# ModuleGliderScore.net
KiCad netlist of a schematic drawn in EAGLE
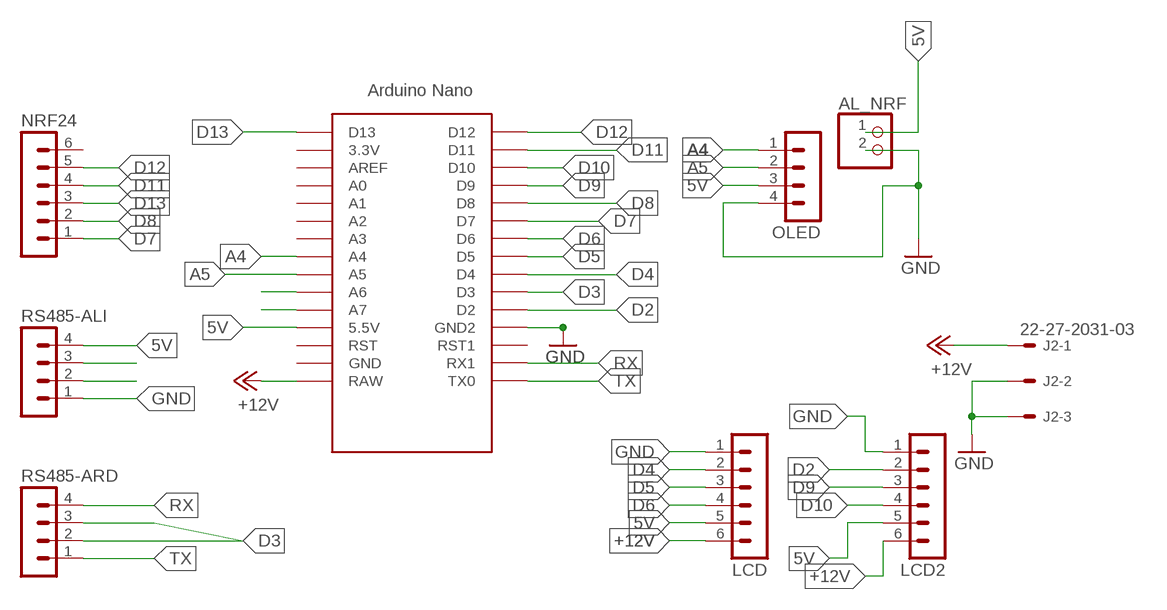
[diagram p0: schematic, sheet 1]

(export (version "E")
  (design (tool "Eeschema 10.0.6"))
  (components
    (comp (ref "AL_NRF")
      (value "PINHD-1X2")
      (footprint "eagle-import:1X02")
      (libsource (lib "eagle-import") (part "PINHD-1X2"))
    )
    (comp (ref "J2")
      (value "22-27-2031-03")
      (footprint "eagle-import:6410-03")
      (libsource (lib "eagle-import") (part "22-?-0327-2031"))
    )
    (comp (ref "LCD")
      (value "MA06-1")
      (footprint "eagle-import:MA06-1")
      (libsource (lib "eagle-import") (part "MA06-1"))
    )
    (comp (ref "LCD2")
      (value "MA06-1")
      (footprint "eagle-import:MA06-1")
      (libsource (lib "eagle-import") (part "MA06-1"))
    )
    (comp (ref "NRF24")
      (value "MA06-1")
      (footprint "eagle-import:MA06-1")
      (libsource (lib "eagle-import") (part "MA06-1"))
    )
    (comp (ref "OLED")
      (value "MA04-1")
      (footprint "eagle-import:MA04-1")
      (libsource (lib "eagle-import") (part "MA04-1"))
    )
    (comp (ref "RS485-ALI")
      (value "MA04-1")
      (footprint "eagle-import:MA04-1")
      (libsource (lib "eagle-import") (part "MA04-1"))
    )
    (comp (ref "RS485-ARD")
      (value "MA04-1")
      (footprint "eagle-import:MA04-1")
      (libsource (lib "eagle-import") (part "MA04-1"))
    )
    (comp (ref "U$1")
      (value "NANO")
      (footprint "eagle-import:NANO")
      (libsource (lib "eagle-import") (part "NANO"))
    )
  )
  (nets
    (net (code "1") (name "+12V") (class "Default")
      (node (ref "J2") (pin "1") (pinfunction "S_1") (pintype "passive"))
      (node (ref "LCD") (pin "6") (pinfunction "6_6") (pintype "passive"))
      (node (ref "LCD2") (pin "6") (pinfunction "6_6") (pintype "passive"))
      (node (ref "U$1") (pin "RAW") (pinfunction "RAW_RAW") (pintype "bidirectional"))
    )
    (net (code "2") (name "5V") (class "Default")
      (node (ref "AL_NRF") (pin "1") (pinfunction "1_1") (pintype "passive"))
      (node (ref "LCD") (pin "5") (pinfunction "5_5") (pintype "passive"))
      (node (ref "LCD2") (pin "5") (pinfunction "5_5") (pintype "passive"))
      (node (ref "OLED") (pin "3") (pinfunction "3_3") (pintype "passive"))
      (node (ref "RS485-ALI") (pin "4") (pinfunction "4_4") (pintype "passive"))
      (node (ref "U$1") (pin "5V") (pinfunction "5.5V_5V") (pintype "bidirectional"))
    )
    (net (code "3") (name "A4") (class "Default")
      (node (ref "OLED") (pin "1") (pinfunction "1_1") (pintype "passive"))
      (node (ref "U$1") (pin "A4") (pinfunction "A4_A4") (pintype "bidirectional"))
    )
    (net (code "4") (name "A5") (class "Default")
      (node (ref "OLED") (pin "2") (pinfunction "2_2") (pintype "passive"))
      (node (ref "U$1") (pin "A5") (pinfunction "A5_A5") (pintype "bidirectional"))
    )
    (net (code "5") (name "D2") (class "Default")
      (node (ref "LCD2") (pin "2") (pinfunction "2_2") (pintype "passive"))
      (node (ref "U$1") (pin "D2") (pinfunction "D2_D2") (pintype "bidirectional"))
    )
    (net (code "6") (name "D3") (class "Default")
      (node (ref "RS485-ARD") (pin "2") (pinfunction "2_2") (pintype "passive"))
      (node (ref "RS485-ARD") (pin "3") (pinfunction "3_3") (pintype "passive"))
      (node (ref "U$1") (pin "D3") (pinfunction "D3_D3") (pintype "bidirectional"))
    )
    (net (code "7") (name "D4") (class "Default")
      (node (ref "LCD") (pin "2") (pinfunction "2_2") (pintype "passive"))
      (node (ref "U$1") (pin "D4") (pinfunction "D4_D4") (pintype "bidirectional"))
    )
    (net (code "8") (name "D5") (class "Default")
      (node (ref "LCD") (pin "3") (pinfunction "3_3") (pintype "passive"))
      (node (ref "U$1") (pin "D5") (pinfunction "D5_D5") (pintype "bidirectional"))
    )
    (net (code "9") (name "D6") (class "Default")
      (node (ref "LCD") (pin "4") (pinfunction "4_4") (pintype "passive"))
      (node (ref "U$1") (pin "D6") (pinfunction "D6_D6") (pintype "bidirectional"))
    )
    (net (code "10") (name "D7") (class "Default")
      (node (ref "NRF24") (pin "1") (pinfunction "1_1") (pintype "passive"))
      (node (ref "U$1") (pin "D7") (pinfunction "D7_D7") (pintype "bidirectional"))
    )
    (net (code "11") (name "D8") (class "Default")
      (node (ref "NRF24") (pin "2") (pinfunction "2_2") (pintype "passive"))
      (node (ref "U$1") (pin "D8") (pinfunction "D8_D8") (pintype "bidirectional"))
    )
    (net (code "12") (name "D9") (class "Default")
      (node (ref "LCD2") (pin "3") (pinfunction "3_3") (pintype "passive"))
      (node (ref "U$1") (pin "D9") (pinfunction "D9_D9") (pintype "bidirectional"))
    )
    (net (code "13") (name "D10") (class "Default")
      (node (ref "LCD2") (pin "4") (pinfunction "4_4") (pintype "passive"))
      (node (ref "U$1") (pin "D10") (pinfunction "D10_D10") (pintype "bidirectional"))
    )
    (net (code "14") (name "D11") (class "Default")
      (node (ref "NRF24") (pin "4") (pinfunction "4_4") (pintype "passive"))
      (node (ref "U$1") (pin "D11") (pinfunction "D11_D11") (pintype "bidirectional"))
    )
    (net (code "15") (name "D12") (class "Default")
      (node (ref "NRF24") (pin "5") (pinfunction "5_5") (pintype "passive"))
      (node (ref "U$1") (pin "D12") (pinfunction "D12_D12") (pintype "bidirectional"))
    )
    (net (code "16") (name "D13") (class "Default")
      (node (ref "NRF24") (pin "3") (pinfunction "3_3") (pintype "passive"))
      (node (ref "U$1") (pin "D13") (pinfunction "D13_D13") (pintype "bidirectional"))
    )
    (net (code "17") (name "GND") (class "Default")
      (node (ref "AL_NRF") (pin "2") (pinfunction "2_2") (pintype "passive"))
      (node (ref "J2") (pin "2") (pinfunction "S_2") (pintype "passive"))
      (node (ref "J2") (pin "3") (pinfunction "S_3") (pintype "passive"))
      (node (ref "LCD") (pin "1") (pinfunction "1_1") (pintype "passive"))
      (node (ref "LCD2") (pin "1") (pinfunction "1_1") (pintype "passive"))
      (node (ref "OLED") (pin "4") (pinfunction "4_4") (pintype "passive"))
      (node (ref "RS485-ALI") (pin "1") (pinfunction "1_1") (pintype "passive"))
      (node (ref "U$1") (pin "GND1") (pinfunction "GND2_GND1") (pintype "bidirectional"))
    )
    (net (code "18") (name "RX") (class "Default")
      (node (ref "RS485-ARD") (pin "4") (pinfunction "4_4") (pintype "passive"))
      (node (ref "U$1") (pin "RX1") (pinfunction "RX1_RX1") (pintype "bidirectional"))
    )
    (net (code "19") (name "TX") (class "Default")
      (node (ref "RS485-ARD") (pin "1") (pinfunction "1_1") (pintype "passive"))
      (node (ref "U$1") (pin "TX0") (pinfunction "TX0_TX0") (pintype "bidirectional"))
    )
    (net (code "20") (name "unconnected-(NRF24-Pad6)") (class "Default")
      (node (ref "NRF24") (pin "6") (pinfunction "6_6") (pintype "passive"))
    )
    (net (code "21") (name "unconnected-(RS485-ALI-Pad2)") (class "Default")
      (node (ref "RS485-ALI") (pin "2") (pinfunction "2_2") (pintype "passive"))
    )
    (net (code "22") (name "unconnected-(RS485-ALI-Pad3)") (class "Default")
      (node (ref "RS485-ALI") (pin "3") (pinfunction "3_3") (pintype "passive"))
    )
    (net (code "23") (name "unconnected-(U$1-Pad3.3V)") (class "Default")
      (node (ref "U$1") (pin "3.3V") (pinfunction "3.3V_3.3V") (pintype "bidirectional"))
    )
    (net (code "24") (name "unconnected-(U$1-PadA0)") (class "Default")
      (node (ref "U$1") (pin "A0") (pinfunction "A0_A0") (pintype "bidirectional"))
    )
    (net (code "25") (name "unconnected-(U$1-PadA1)") (class "Default")
      (node (ref "U$1") (pin "A1") (pinfunction "A1_A1") (pintype "bidirectional"))
    )
    (net (code "26") (name "unconnected-(U$1-PadA2)") (class "Default")
      (node (ref "U$1") (pin "A2") (pinfunction "A2_A2") (pintype "bidirectional"))
    )
    (net (code "27") (name "unconnected-(U$1-PadA3)") (class "Default")
      (node (ref "U$1") (pin "A3") (pinfunction "A3_A3") (pintype "bidirectional"))
    )
    (net (code "28") (name "unconnected-(U$1-PadA6)") (class "Default")
      (node (ref "U$1") (pin "A6") (pinfunction "A6_A6") (pintype "bidirectional"))
    )
    (net (code "29") (name "unconnected-(U$1-PadA7)") (class "Default")
      (node (ref "U$1") (pin "A7") (pinfunction "A7_A7") (pintype "bidirectional"))
    )
    (net (code "30") (name "unconnected-(U$1-PadAREF)") (class "Default")
      (node (ref "U$1") (pin "AREF") (pinfunction "AREF_AREF") (pintype "bidirectional"))
    )
    (net (code "31") (name "unconnected-(U$1-PadGND)") (class "Default")
      (node (ref "U$1") (pin "GND") (pinfunction "GND_GND") (pintype "bidirectional"))
    )
    (net (code "32") (name "unconnected-(U$1-PadICSP1)") (class "Default")
      (node (ref "U$1") (pin "ICSP1") (pinfunction "ICSP1_ICSP1") (pintype "bidirectional"))
    )
    (net (code "33") (name "unconnected-(U$1-PadICSP2)") (class "Default")
      (node (ref "U$1") (pin "ICSP2") (pinfunction "ICSP2_ICSP2") (pintype "bidirectional"))
    )
    (net (code "34") (name "unconnected-(U$1-PadICSP3)") (class "Default")
      (node (ref "U$1") (pin "ICSP3") (pinfunction "ICSP3_ICSP3") (pintype "bidirectional"))
    )
    (net (code "35") (name "unconnected-(U$1-PadICSP4)") (class "Default")
      (node (ref "U$1") (pin "ICSP4") (pinfunction "ICSP4_ICSP4") (pintype "bidirectional"))
    )
    (net (code "36") (name "unconnected-(U$1-PadICSP5)") (class "Default")
      (node (ref "U$1") (pin "ICSP5") (pinfunction "ICSP5_ICSP5") (pintype "bidirectional"))
    )
    (net (code "37") (name "unconnected-(U$1-PadICSP6)") (class "Default")
      (node (ref "U$1") (pin "ICSP6") (pinfunction "ICSP6_ICSP6") (pintype "bidirectional"))
    )
    (net (code "38") (name "unconnected-(U$1-PadRST)") (class "Default")
      (node (ref "U$1") (pin "RST") (pinfunction "RST_RST") (pintype "bidirectional"))
    )
    (net (code "39") (name "unconnected-(U$1-PadRST1)") (class "Default")
      (node (ref "U$1") (pin "RST1") (pinfunction "RST1_RST1") (pintype "bidirectional"))
    )
  )
)
